# Sheet1.net
KiCad netlist of a schematic drawn in Altium Designer
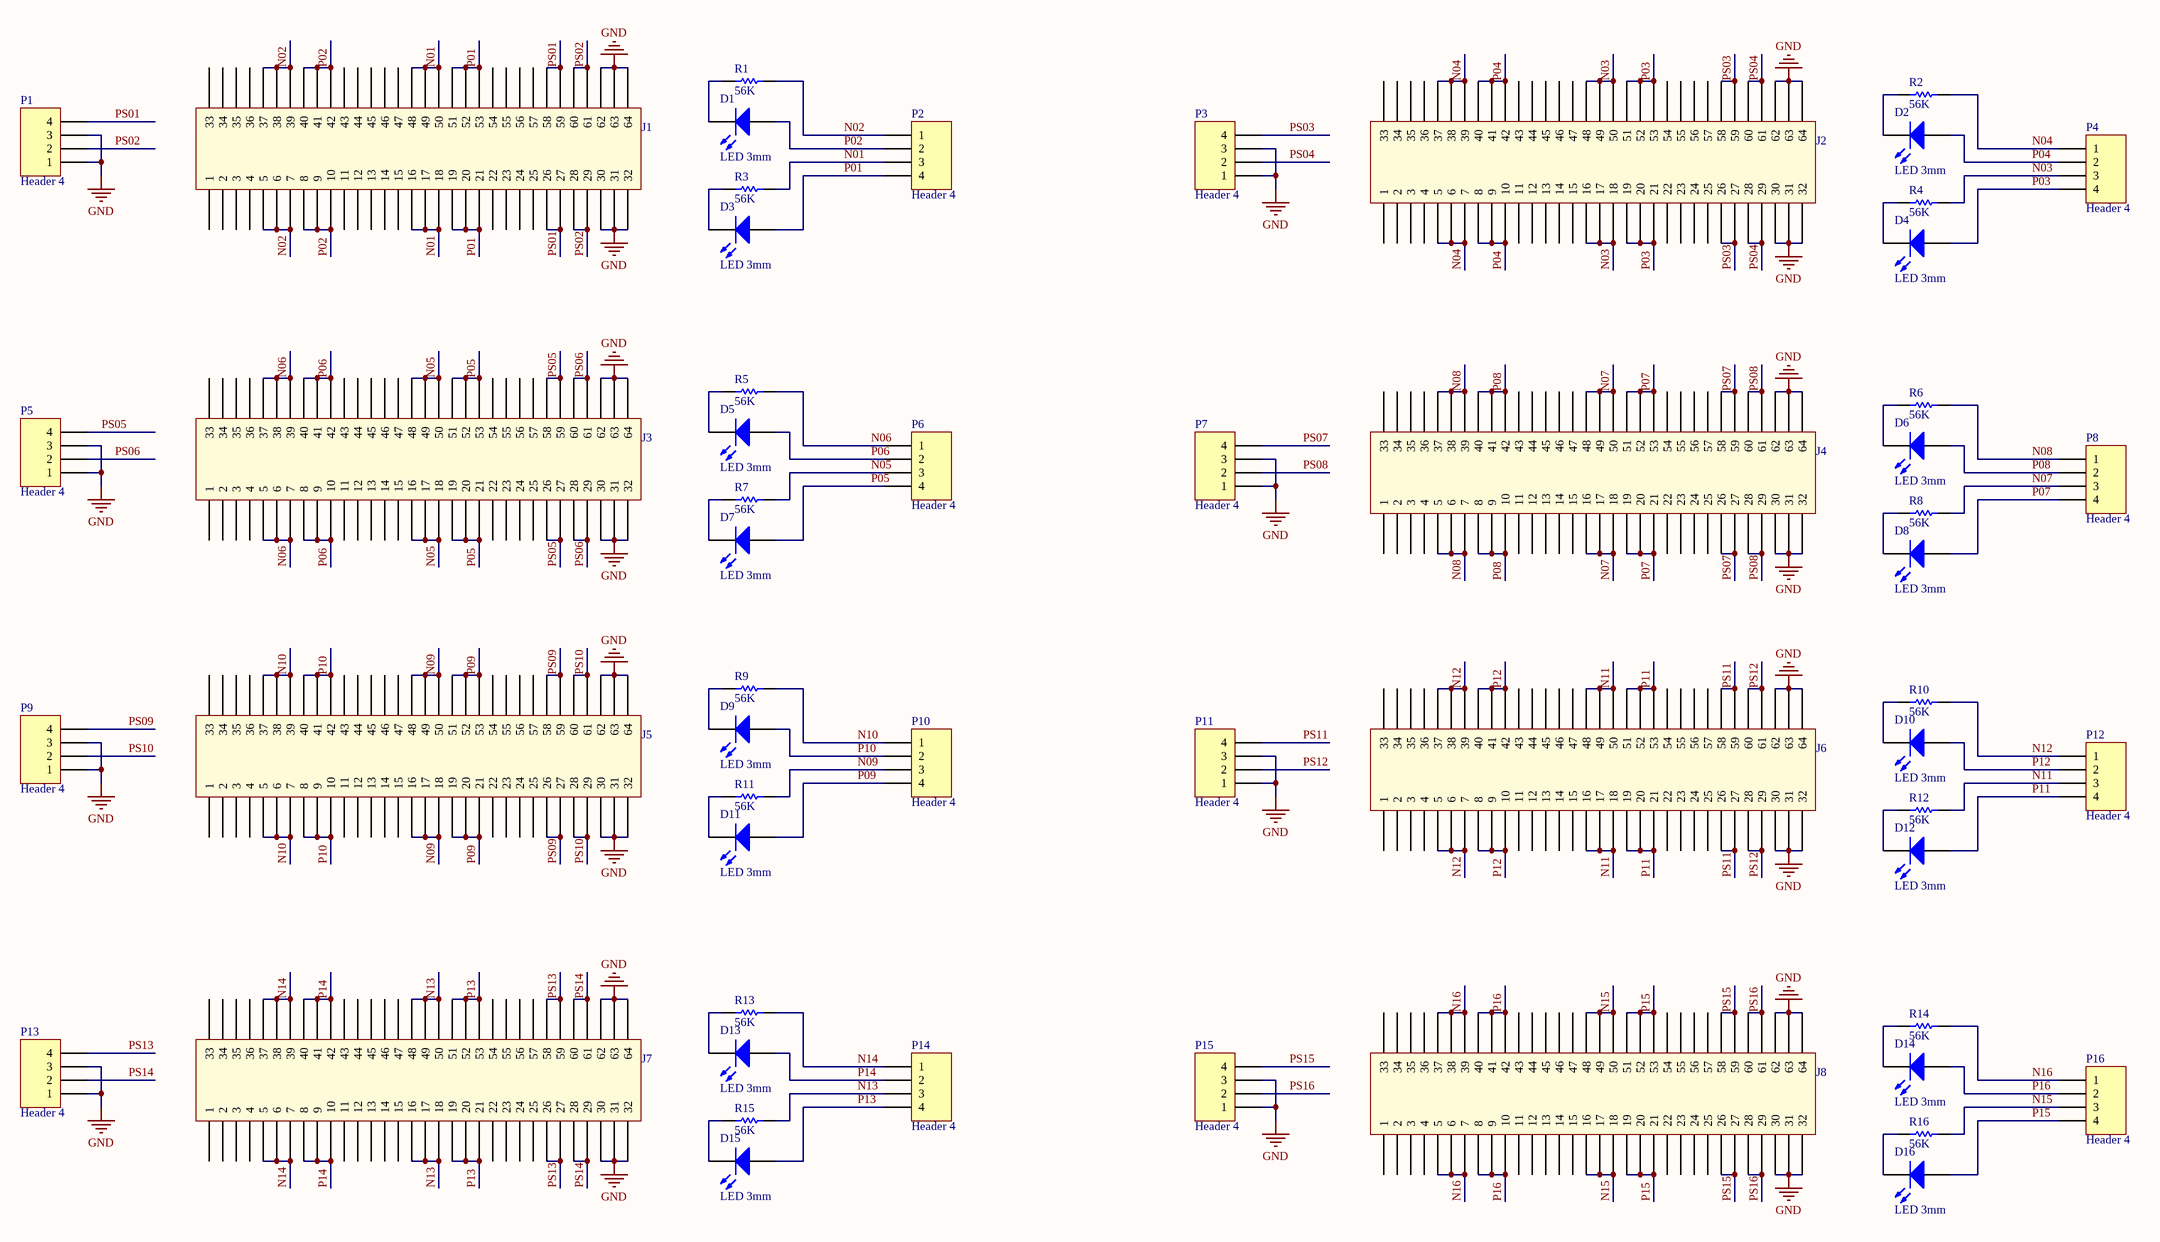
[diagram p0: Sheet1.SchDoc]

(export (version "E")
  (design (tool "Eeschema 10.0.6"))
  (components
    (comp (ref "D1")
      (value "LED 3mm")
      (footprint "Led 3mm")
      (description "Typical INFRARED GaAs LED")
      (fields (field (name "PUBLISHER") "Altium Limited"))
      (libsource (lib "Miscellaneous Devices") (part "LED0"))
    )
    (comp (ref "D2")
      (value "LED 3mm")
      (footprint "Led 3mm")
      (description "Typical INFRARED GaAs LED")
      (fields (field (name "PUBLISHER") "Altium Limited"))
      (libsource (lib "Miscellaneous Devices") (part "LED0"))
    )
    (comp (ref "D3")
      (value "LED 3mm")
      (footprint "Led 3mm")
      (description "Typical INFRARED GaAs LED")
      (fields (field (name "PUBLISHER") "Altium Limited"))
      (libsource (lib "Miscellaneous Devices") (part "LED0"))
    )
    (comp (ref "D4")
      (value "LED 3mm")
      (footprint "Led 3mm")
      (description "Typical INFRARED GaAs LED")
      (fields (field (name "PUBLISHER") "Altium Limited"))
      (libsource (lib "Miscellaneous Devices") (part "LED0"))
    )
    (comp (ref "D5")
      (value "LED 3mm")
      (footprint "Led 3mm")
      (description "Typical INFRARED GaAs LED")
      (fields (field (name "PUBLISHER") "Altium Limited"))
      (libsource (lib "Miscellaneous Devices") (part "LED0"))
    )
    (comp (ref "D6")
      (value "LED 3mm")
      (footprint "Led 3mm")
      (description "Typical INFRARED GaAs LED")
      (fields (field (name "PUBLISHER") "Altium Limited"))
      (libsource (lib "Miscellaneous Devices") (part "LED0"))
    )
    (comp (ref "D7")
      (value "LED 3mm")
      (footprint "Led 3mm")
      (description "Typical INFRARED GaAs LED")
      (fields (field (name "PUBLISHER") "Altium Limited"))
      (libsource (lib "Miscellaneous Devices") (part "LED0"))
    )
    (comp (ref "D8")
      (value "LED 3mm")
      (footprint "Led 3mm")
      (description "Typical INFRARED GaAs LED")
      (fields (field (name "PUBLISHER") "Altium Limited"))
      (libsource (lib "Miscellaneous Devices") (part "LED0"))
    )
    (comp (ref "D9")
      (value "LED 3mm")
      (footprint "Led 3mm")
      (description "Typical INFRARED GaAs LED")
      (fields (field (name "PUBLISHER") "Altium Limited"))
      (libsource (lib "Miscellaneous Devices") (part "LED0"))
    )
    (comp (ref "D10")
      (value "LED 3mm")
      (footprint "Led 3mm")
      (description "Typical INFRARED GaAs LED")
      (fields (field (name "PUBLISHER") "Altium Limited"))
      (libsource (lib "Miscellaneous Devices") (part "LED0"))
    )
    (comp (ref "D11")
      (value "LED 3mm")
      (footprint "Led 3mm")
      (description "Typical INFRARED GaAs LED")
      (fields (field (name "PUBLISHER") "Altium Limited"))
      (libsource (lib "Miscellaneous Devices") (part "LED0"))
    )
    (comp (ref "D12")
      (value "LED 3mm")
      (footprint "Led 3mm")
      (description "Typical INFRARED GaAs LED")
      (fields (field (name "PUBLISHER") "Altium Limited"))
      (libsource (lib "Miscellaneous Devices") (part "LED0"))
    )
    (comp (ref "D13")
      (value "LED 3mm")
      (footprint "Led 3mm")
      (description "Typical INFRARED GaAs LED")
      (fields (field (name "PUBLISHER") "Altium Limited"))
      (libsource (lib "Miscellaneous Devices") (part "LED0"))
    )
    (comp (ref "D14")
      (value "LED 3mm")
      (footprint "Led 3mm")
      (description "Typical INFRARED GaAs LED")
      (fields (field (name "PUBLISHER") "Altium Limited"))
      (libsource (lib "Miscellaneous Devices") (part "LED0"))
    )
    (comp (ref "D15")
      (value "LED 3mm")
      (footprint "Led 3mm")
      (description "Typical INFRARED GaAs LED")
      (fields (field (name "PUBLISHER") "Altium Limited"))
      (libsource (lib "Miscellaneous Devices") (part "LED0"))
    )
    (comp (ref "D16")
      (value "LED 3mm")
      (footprint "Led 3mm")
      (description "Typical INFRARED GaAs LED")
      (fields (field (name "PUBLISHER") "Altium Limited"))
      (libsource (lib "Miscellaneous Devices") (part "LED0"))
    )
    (comp (ref "J1")
      (value "Header 32x2")
      (footprint "Header32x2")
      (libsource (lib "dung_maker_2018") (part "Header 32x2"))
    )
    (comp (ref "J2")
      (value "Header 32x2")
      (footprint "Header32x2")
      (libsource (lib "dung_maker_2018") (part "Header 32x2"))
    )
    (comp (ref "J3")
      (value "Header 32x2")
      (footprint "Header32x2")
      (libsource (lib "dung_maker_2018") (part "Header 32x2"))
    )
    (comp (ref "J4")
      (value "Header 32x2")
      (footprint "Header32x2")
      (libsource (lib "dung_maker_2018") (part "Header 32x2"))
    )
    (comp (ref "J5")
      (value "Header 32x2")
      (footprint "Header32x2")
      (libsource (lib "dung_maker_2018") (part "Header 32x2"))
    )
    (comp (ref "J6")
      (value "Header 32x2")
      (footprint "Header32x2")
      (libsource (lib "dung_maker_2018") (part "Header 32x2"))
    )
    (comp (ref "J7")
      (value "Header 32x2")
      (footprint "Header32x2")
      (libsource (lib "dung_maker_2018") (part "Header 32x2"))
    )
    (comp (ref "J8")
      (value "Header 32x2")
      (footprint "Header32x2")
      (libsource (lib "dung_maker_2018") (part "Header 32x2"))
    )
    (comp (ref "P1")
      (value "Header 4")
      (footprint "CON4")
      (description "Header, 4-Pin")
      (fields (field (name "PUBLISHER") "Altium Limited"))
      (libsource (lib "Miscellaneous Connectors") (part "Header 4"))
    )
    (comp (ref "P2")
      (value "Header 4")
      (footprint "CON4")
      (description "Header, 4-Pin")
      (fields (field (name "PUBLISHER") "Altium Limited"))
      (libsource (lib "") (part "Header 4_1"))
    )
    (comp (ref "P3")
      (value "Header 4")
      (footprint "CON4")
      (description "Header, 4-Pin")
      (fields (field (name "PUBLISHER") "Altium Limited"))
      (libsource (lib "Miscellaneous Connectors") (part "Header 4"))
    )
    (comp (ref "P4")
      (value "Header 4")
      (footprint "CON4")
      (description "Header, 4-Pin")
      (fields (field (name "PUBLISHER") "Altium Limited"))
      (libsource (lib "") (part "Header 4_1"))
    )
    (comp (ref "P5")
      (value "Header 4")
      (footprint "CON4")
      (description "Header, 4-Pin")
      (fields (field (name "PUBLISHER") "Altium Limited"))
      (libsource (lib "Miscellaneous Connectors") (part "Header 4"))
    )
    (comp (ref "P6")
      (value "Header 4")
      (footprint "CON4")
      (description "Header, 4-Pin")
      (fields (field (name "PUBLISHER") "Altium Limited"))
      (libsource (lib "") (part "Header 4_1"))
    )
    (comp (ref "P7")
      (value "Header 4")
      (footprint "CON4")
      (description "Header, 4-Pin")
      (fields (field (name "PUBLISHER") "Altium Limited"))
      (libsource (lib "Miscellaneous Connectors") (part "Header 4"))
    )
    (comp (ref "P8")
      (value "Header 4")
      (footprint "CON4")
      (description "Header, 4-Pin")
      (fields (field (name "PUBLISHER") "Altium Limited"))
      (libsource (lib "") (part "Header 4_1"))
    )
    (comp (ref "P9")
      (value "Header 4")
      (footprint "CON4")
      (description "Header, 4-Pin")
      (fields (field (name "PUBLISHER") "Altium Limited"))
      (libsource (lib "Miscellaneous Connectors") (part "Header 4"))
    )
    (comp (ref "P10")
      (value "Header 4")
      (footprint "CON4")
      (description "Header, 4-Pin")
      (fields (field (name "PUBLISHER") "Altium Limited"))
      (libsource (lib "") (part "Header 4_1"))
    )
    (comp (ref "P11")
      (value "Header 4")
      (footprint "CON4")
      (description "Header, 4-Pin")
      (fields (field (name "PUBLISHER") "Altium Limited"))
      (libsource (lib "Miscellaneous Connectors") (part "Header 4"))
    )
    (comp (ref "P12")
      (value "Header 4")
      (footprint "CON4")
      (description "Header, 4-Pin")
      (fields (field (name "PUBLISHER") "Altium Limited"))
      (libsource (lib "") (part "Header 4_1"))
    )
    (comp (ref "P13")
      (value "Header 4")
      (footprint "CON4")
      (description "Header, 4-Pin")
      (fields (field (name "PUBLISHER") "Altium Limited"))
      (libsource (lib "Miscellaneous Connectors") (part "Header 4"))
    )
    (comp (ref "P14")
      (value "Header 4")
      (footprint "CON4")
      (description "Header, 4-Pin")
      (fields (field (name "PUBLISHER") "Altium Limited"))
      (libsource (lib "") (part "Header 4_1"))
    )
    (comp (ref "P15")
      (value "Header 4")
      (footprint "CON4")
      (description "Header, 4-Pin")
      (fields (field (name "PUBLISHER") "Altium Limited"))
      (libsource (lib "Miscellaneous Connectors") (part "Header 4"))
    )
    (comp (ref "P16")
      (value "Header 4")
      (footprint "CON4")
      (description "Header, 4-Pin")
      (fields (field (name "PUBLISHER") "Altium Limited"))
      (libsource (lib "") (part "Header 4_1"))
    )
    (comp (ref "R1")
      (value "56K")
      (footprint "R1/8W")
      (description "Resistor")
      (fields (field (name "Comment") "Res1") (field (name "PUBLISHER") "Altium Limited"))
      (libsource (lib "Miscellaneous Devices") (part "Res1"))
    )
    (comp (ref "R2")
      (value "56K")
      (footprint "R1/8W")
      (description "Resistor")
      (fields (field (name "Comment") "Res1") (field (name "PUBLISHER") "Altium Limited"))
      (libsource (lib "Miscellaneous Devices") (part "Res1"))
    )
    (comp (ref "R3")
      (value "56K")
      (footprint "R1/8W")
      (description "Resistor")
      (fields (field (name "Comment") "Res1") (field (name "PUBLISHER") "Altium Limited"))
      (libsource (lib "Miscellaneous Devices") (part "Res1"))
    )
    (comp (ref "R4")
      (value "56K")
      (footprint "R1/8W")
      (description "Resistor")
      (fields (field (name "Comment") "Res1") (field (name "PUBLISHER") "Altium Limited"))
      (libsource (lib "Miscellaneous Devices") (part "Res1"))
    )
    (comp (ref "R5")
      (value "56K")
      (footprint "R1/8W")
      (description "Resistor")
      (fields (field (name "Comment") "Res1") (field (name "PUBLISHER") "Altium Limited"))
      (libsource (lib "Miscellaneous Devices") (part "Res1"))
    )
    (comp (ref "R6")
      (value "56K")
      (footprint "R1/8W")
      (description "Resistor")
      (fields (field (name "Comment") "Res1") (field (name "PUBLISHER") "Altium Limited"))
      (libsource (lib "Miscellaneous Devices") (part "Res1"))
    )
    (comp (ref "R7")
      (value "56K")
      (footprint "R1/8W")
      (description "Resistor")
      (fields (field (name "Comment") "Res1") (field (name "PUBLISHER") "Altium Limited"))
      (libsource (lib "Miscellaneous Devices") (part "Res1"))
    )
    (comp (ref "R8")
      (value "56K")
      (footprint "R1/8W")
      (description "Resistor")
      (fields (field (name "Comment") "Res1") (field (name "PUBLISHER") "Altium Limited"))
      (libsource (lib "Miscellaneous Devices") (part "Res1"))
    )
    (comp (ref "R9")
      (value "56K")
      (footprint "R1/8W")
      (description "Resistor")
      (fields (field (name "Comment") "Res1") (field (name "PUBLISHER") "Altium Limited"))
      (libsource (lib "Miscellaneous Devices") (part "Res1"))
    )
    (comp (ref "R10")
      (value "56K")
      (footprint "R1/8W")
      (description "Resistor")
      (fields (field (name "Comment") "Res1") (field (name "PUBLISHER") "Altium Limited"))
      (libsource (lib "Miscellaneous Devices") (part "Res1"))
    )
    (comp (ref "R11")
      (value "56K")
      (footprint "R1/8W")
      (description "Resistor")
      (fields (field (name "Comment") "Res1") (field (name "PUBLISHER") "Altium Limited"))
      (libsource (lib "Miscellaneous Devices") (part "Res1"))
    )
    (comp (ref "R12")
      (value "56K")
      (footprint "R1/8W")
      (description "Resistor")
      (fields (field (name "Comment") "Res1") (field (name "PUBLISHER") "Altium Limited"))
      (libsource (lib "Miscellaneous Devices") (part "Res1"))
    )
    (comp (ref "R13")
      (value "56K")
      (footprint "R1/8W")
      (description "Resistor")
      (fields (field (name "Comment") "Res1") (field (name "PUBLISHER") "Altium Limited"))
      (libsource (lib "Miscellaneous Devices") (part "Res1"))
    )
    (comp (ref "R14")
      (value "56K")
      (footprint "R1/8W")
      (description "Resistor")
      (fields (field (name "Comment") "Res1") (field (name "PUBLISHER") "Altium Limited"))
      (libsource (lib "Miscellaneous Devices") (part "Res1"))
    )
    (comp (ref "R15")
      (value "56K")
      (footprint "R1/8W")
      (description "Resistor")
      (fields (field (name "Comment") "Res1") (field (name "PUBLISHER") "Altium Limited"))
      (libsource (lib "Miscellaneous Devices") (part "Res1"))
    )
    (comp (ref "R16")
      (value "56K")
      (footprint "R1/8W")
      (description "Resistor")
      (fields (field (name "Comment") "Res1") (field (name "PUBLISHER") "Altium Limited"))
      (libsource (lib "Miscellaneous Devices") (part "Res1"))
    )
  )
  (nets
    (net (code "1") (name "/N01") (class "Default")
      (node (ref "J1") (pin "16") (pinfunction "16_16") (pintype "passive"))
      (node (ref "J1") (pin "17") (pinfunction "17_17") (pintype "passive"))
      (node (ref "J1") (pin "18") (pinfunction "18_18") (pintype "passive"))
      (node (ref "J1") (pin "48") (pinfunction "48_48") (pintype "passive"))
      (node (ref "J1") (pin "49") (pinfunction "49_49") (pintype "passive"))
      (node (ref "J1") (pin "50") (pinfunction "50_50") (pintype "passive"))
      (node (ref "P2") (pin "3") (pinfunction "3_3") (pintype "passive"))
      (node (ref "R3") (pin "1") (pinfunction "1_1") (pintype "passive"))
    )
    (net (code "2") (name "/N02") (class "Default")
      (node (ref "J1") (pin "37") (pinfunction "37_37") (pintype "passive"))
      (node (ref "J1") (pin "38") (pinfunction "38_38") (pintype "passive"))
      (node (ref "J1") (pin "39") (pinfunction "39_39") (pintype "passive"))
      (node (ref "J1") (pin "5") (pinfunction "5_5") (pintype "passive"))
      (node (ref "J1") (pin "6") (pinfunction "6_6") (pintype "passive"))
      (node (ref "J1") (pin "7") (pinfunction "7_7") (pintype "passive"))
      (node (ref "P2") (pin "1") (pinfunction "1_1") (pintype "passive"))
      (node (ref "R1") (pin "1") (pinfunction "1_1") (pintype "passive"))
    )
    (net (code "3") (name "/N03") (class "Default")
      (node (ref "J2") (pin "16") (pinfunction "16_16") (pintype "passive"))
      (node (ref "J2") (pin "17") (pinfunction "17_17") (pintype "passive"))
      (node (ref "J2") (pin "18") (pinfunction "18_18") (pintype "passive"))
      (node (ref "J2") (pin "48") (pinfunction "48_48") (pintype "passive"))
      (node (ref "J2") (pin "49") (pinfunction "49_49") (pintype "passive"))
      (node (ref "J2") (pin "50") (pinfunction "50_50") (pintype "passive"))
      (node (ref "P4") (pin "3") (pinfunction "3_3") (pintype "passive"))
      (node (ref "R4") (pin "1") (pinfunction "1_1") (pintype "passive"))
    )
    (net (code "4") (name "/N04") (class "Default")
      (node (ref "J2") (pin "37") (pinfunction "37_37") (pintype "passive"))
      (node (ref "J2") (pin "38") (pinfunction "38_38") (pintype "passive"))
      (node (ref "J2") (pin "39") (pinfunction "39_39") (pintype "passive"))
      (node (ref "J2") (pin "5") (pinfunction "5_5") (pintype "passive"))
      (node (ref "J2") (pin "6") (pinfunction "6_6") (pintype "passive"))
      (node (ref "J2") (pin "7") (pinfunction "7_7") (pintype "passive"))
      (node (ref "P4") (pin "1") (pinfunction "1_1") (pintype "passive"))
      (node (ref "R2") (pin "1") (pinfunction "1_1") (pintype "passive"))
    )
    (net (code "5") (name "/N05") (class "Default")
      (node (ref "J3") (pin "16") (pinfunction "16_16") (pintype "passive"))
      (node (ref "J3") (pin "17") (pinfunction "17_17") (pintype "passive"))
      (node (ref "J3") (pin "18") (pinfunction "18_18") (pintype "passive"))
      (node (ref "J3") (pin "48") (pinfunction "48_48") (pintype "passive"))
      (node (ref "J3") (pin "49") (pinfunction "49_49") (pintype "passive"))
      (node (ref "J3") (pin "50") (pinfunction "50_50") (pintype "passive"))
      (node (ref "P6") (pin "3") (pinfunction "3_3") (pintype "passive"))
      (node (ref "R7") (pin "1") (pinfunction "1_1") (pintype "passive"))
    )
    (net (code "6") (name "/N06") (class "Default")
      (node (ref "J3") (pin "37") (pinfunction "37_37") (pintype "passive"))
      (node (ref "J3") (pin "38") (pinfunction "38_38") (pintype "passive"))
      (node (ref "J3") (pin "39") (pinfunction "39_39") (pintype "passive"))
      (node (ref "J3") (pin "5") (pinfunction "5_5") (pintype "passive"))
      (node (ref "J3") (pin "6") (pinfunction "6_6") (pintype "passive"))
      (node (ref "J3") (pin "7") (pinfunction "7_7") (pintype "passive"))
      (node (ref "P6") (pin "1") (pinfunction "1_1") (pintype "passive"))
      (node (ref "R5") (pin "1") (pinfunction "1_1") (pintype "passive"))
    )
    (net (code "7") (name "/N07") (class "Default")
      (node (ref "J4") (pin "16") (pinfunction "16_16") (pintype "passive"))
      (node (ref "J4") (pin "17") (pinfunction "17_17") (pintype "passive"))
      (node (ref "J4") (pin "18") (pinfunction "18_18") (pintype "passive"))
      (node (ref "J4") (pin "48") (pinfunction "48_48") (pintype "passive"))
      (node (ref "J4") (pin "49") (pinfunction "49_49") (pintype "passive"))
      (node (ref "J4") (pin "50") (pinfunction "50_50") (pintype "passive"))
      (node (ref "P8") (pin "3") (pinfunction "3_3") (pintype "passive"))
      (node (ref "R8") (pin "1") (pinfunction "1_1") (pintype "passive"))
    )
    (net (code "8") (name "/N08") (class "Default")
      (node (ref "J4") (pin "37") (pinfunction "37_37") (pintype "passive"))
      (node (ref "J4") (pin "38") (pinfunction "38_38") (pintype "passive"))
      (node (ref "J4") (pin "39") (pinfunction "39_39") (pintype "passive"))
      (node (ref "J4") (pin "5") (pinfunction "5_5") (pintype "passive"))
      (node (ref "J4") (pin "6") (pinfunction "6_6") (pintype "passive"))
      (node (ref "J4") (pin "7") (pinfunction "7_7") (pintype "passive"))
      (node (ref "P8") (pin "1") (pinfunction "1_1") (pintype "passive"))
      (node (ref "R6") (pin "1") (pinfunction "1_1") (pintype "passive"))
    )
    (net (code "9") (name "/N09") (class "Default")
      (node (ref "J5") (pin "16") (pinfunction "16_16") (pintype "passive"))
      (node (ref "J5") (pin "17") (pinfunction "17_17") (pintype "passive"))
      (node (ref "J5") (pin "18") (pinfunction "18_18") (pintype "passive"))
      (node (ref "J5") (pin "48") (pinfunction "48_48") (pintype "passive"))
      (node (ref "J5") (pin "49") (pinfunction "49_49") (pintype "passive"))
      (node (ref "J5") (pin "50") (pinfunction "50_50") (pintype "passive"))
      (node (ref "P10") (pin "3") (pinfunction "3_3") (pintype "passive"))
      (node (ref "R11") (pin "1") (pinfunction "1_1") (pintype "passive"))
    )
    (net (code "10") (name "/N10") (class "Default")
      (node (ref "J5") (pin "37") (pinfunction "37_37") (pintype "passive"))
      (node (ref "J5") (pin "38") (pinfunction "38_38") (pintype "passive"))
      (node (ref "J5") (pin "39") (pinfunction "39_39") (pintype "passive"))
      (node (ref "J5") (pin "5") (pinfunction "5_5") (pintype "passive"))
      (node (ref "J5") (pin "6") (pinfunction "6_6") (pintype "passive"))
      (node (ref "J5") (pin "7") (pinfunction "7_7") (pintype "passive"))
      (node (ref "P10") (pin "1") (pinfunction "1_1") (pintype "passive"))
      (node (ref "R9") (pin "1") (pinfunction "1_1") (pintype "passive"))
    )
    (net (code "11") (name "/N11") (class "Default")
      (node (ref "J6") (pin "16") (pinfunction "16_16") (pintype "passive"))
      (node (ref "J6") (pin "17") (pinfunction "17_17") (pintype "passive"))
      (node (ref "J6") (pin "18") (pinfunction "18_18") (pintype "passive"))
      (node (ref "J6") (pin "48") (pinfunction "48_48") (pintype "passive"))
      (node (ref "J6") (pin "49") (pinfunction "49_49") (pintype "passive"))
      (node (ref "J6") (pin "50") (pinfunction "50_50") (pintype "passive"))
      (node (ref "P12") (pin "3") (pinfunction "3_3") (pintype "passive"))
      (node (ref "R12") (pin "1") (pinfunction "1_1") (pintype "passive"))
    )
    (net (code "12") (name "/N12") (class "Default")
      (node (ref "J6") (pin "37") (pinfunction "37_37") (pintype "passive"))
      (node (ref "J6") (pin "38") (pinfunction "38_38") (pintype "passive"))
      (node (ref "J6") (pin "39") (pinfunction "39_39") (pintype "passive"))
      (node (ref "J6") (pin "5") (pinfunction "5_5") (pintype "passive"))
      (node (ref "J6") (pin "6") (pinfunction "6_6") (pintype "passive"))
      (node (ref "J6") (pin "7") (pinfunction "7_7") (pintype "passive"))
      (node (ref "P12") (pin "1") (pinfunction "1_1") (pintype "passive"))
      (node (ref "R10") (pin "1") (pinfunction "1_1") (pintype "passive"))
    )
    (net (code "13") (name "/N13") (class "Default")
      (node (ref "J7") (pin "16") (pinfunction "16_16") (pintype "passive"))
      (node (ref "J7") (pin "17") (pinfunction "17_17") (pintype "passive"))
      (node (ref "J7") (pin "18") (pinfunction "18_18") (pintype "passive"))
      (node (ref "J7") (pin "48") (pinfunction "48_48") (pintype "passive"))
      (node (ref "J7") (pin "49") (pinfunction "49_49") (pintype "passive"))
      (node (ref "J7") (pin "50") (pinfunction "50_50") (pintype "passive"))
      (node (ref "P14") (pin "3") (pinfunction "3_3") (pintype "passive"))
      (node (ref "R15") (pin "1") (pinfunction "1_1") (pintype "passive"))
    )
    (net (code "14") (name "/N14") (class "Default")
      (node (ref "J7") (pin "37") (pinfunction "37_37") (pintype "passive"))
      (node (ref "J7") (pin "38") (pinfunction "38_38") (pintype "passive"))
      (node (ref "J7") (pin "39") (pinfunction "39_39") (pintype "passive"))
      (node (ref "J7") (pin "5") (pinfunction "5_5") (pintype "passive"))
      (node (ref "J7") (pin "6") (pinfunction "6_6") (pintype "passive"))
      (node (ref "J7") (pin "7") (pinfunction "7_7") (pintype "passive"))
      (node (ref "P14") (pin "1") (pinfunction "1_1") (pintype "passive"))
      (node (ref "R13") (pin "1") (pinfunction "1_1") (pintype "passive"))
    )
    (net (code "15") (name "/N15") (class "Default")
      (node (ref "J8") (pin "16") (pinfunction "16_16") (pintype "passive"))
      (node (ref "J8") (pin "17") (pinfunction "17_17") (pintype "passive"))
      (node (ref "J8") (pin "18") (pinfunction "18_18") (pintype "passive"))
      (node (ref "J8") (pin "48") (pinfunction "48_48") (pintype "passive"))
      (node (ref "J8") (pin "49") (pinfunction "49_49") (pintype "passive"))
      (node (ref "J8") (pin "50") (pinfunction "50_50") (pintype "passive"))
      (node (ref "P16") (pin "3") (pinfunction "3_3") (pintype "passive"))
      (node (ref "R16") (pin "1") (pinfunction "1_1") (pintype "passive"))
    )
    (net (code "16") (name "/N16") (class "Default")
      (node (ref "J8") (pin "37") (pinfunction "37_37") (pintype "passive"))
      (node (ref "J8") (pin "38") (pinfunction "38_38") (pintype "passive"))
      (node (ref "J8") (pin "39") (pinfunction "39_39") (pintype "passive"))
      (node (ref "J8") (pin "5") (pinfunction "5_5") (pintype "passive"))
      (node (ref "J8") (pin "6") (pinfunction "6_6") (pintype "passive"))
      (node (ref "J8") (pin "7") (pinfunction "7_7") (pintype "passive"))
      (node (ref "P16") (pin "1") (pinfunction "1_1") (pintype "passive"))
      (node (ref "R14") (pin "1") (pinfunction "1_1") (pintype "passive"))
    )
    (net (code "17") (name "/P01") (class "Default")
      (node (ref "D3") (pin "1") (pinfunction "A_1") (pintype "passive"))
      (node (ref "J1") (pin "19") (pinfunction "19_19") (pintype "passive"))
      (node (ref "J1") (pin "20") (pinfunction "20_20") (pintype "passive"))
      (node (ref "J1") (pin "21") (pinfunction "21_21") (pintype "passive"))
      (node (ref "J1") (pin "51") (pinfunction "51_51") (pintype "passive"))
      (node (ref "J1") (pin "52") (pinfunction "52_52") (pintype "passive"))
      (node (ref "J1") (pin "53") (pinfunction "53_53") (pintype "passive"))
      (node (ref "P2") (pin "4") (pinfunction "4_4") (pintype "passive"))
    )
    (net (code "18") (name "/P02") (class "Default")
      (node (ref "D1") (pin "1") (pinfunction "A_1") (pintype "passive"))
      (node (ref "J1") (pin "10") (pinfunction "10_10") (pintype "passive"))
      (node (ref "J1") (pin "40") (pinfunction "40_40") (pintype "passive"))
      (node (ref "J1") (pin "41") (pinfunction "41_41") (pintype "passive"))
      (node (ref "J1") (pin "42") (pinfunction "42_42") (pintype "passive"))
      (node (ref "J1") (pin "8") (pinfunction "8_8") (pintype "passive"))
      (node (ref "J1") (pin "9") (pinfunction "9_9") (pintype "passive"))
      (node (ref "P2") (pin "2") (pinfunction "2_2") (pintype "passive"))
    )
    (net (code "19") (name "/P03") (class "Default")
      (node (ref "D4") (pin "1") (pinfunction "A_1") (pintype "passive"))
      (node (ref "J2") (pin "19") (pinfunction "19_19") (pintype "passive"))
      (node (ref "J2") (pin "20") (pinfunction "20_20") (pintype "passive"))
      (node (ref "J2") (pin "21") (pinfunction "21_21") (pintype "passive"))
      (node (ref "J2") (pin "51") (pinfunction "51_51") (pintype "passive"))
      (node (ref "J2") (pin "52") (pinfunction "52_52") (pintype "passive"))
      (node (ref "J2") (pin "53") (pinfunction "53_53") (pintype "passive"))
      (node (ref "P4") (pin "4") (pinfunction "4_4") (pintype "passive"))
    )
    (net (code "20") (name "/P04") (class "Default")
      (node (ref "D2") (pin "1") (pinfunction "A_1") (pintype "passive"))
      (node (ref "J2") (pin "10") (pinfunction "10_10") (pintype "passive"))
      (node (ref "J2") (pin "40") (pinfunction "40_40") (pintype "passive"))
      (node (ref "J2") (pin "41") (pinfunction "41_41") (pintype "passive"))
      (node (ref "J2") (pin "42") (pinfunction "42_42") (pintype "passive"))
      (node (ref "J2") (pin "8") (pinfunction "8_8") (pintype "passive"))
      (node (ref "J2") (pin "9") (pinfunction "9_9") (pintype "passive"))
      (node (ref "P4") (pin "2") (pinfunction "2_2") (pintype "passive"))
    )
    (net (code "21") (name "/P05") (class "Default")
      (node (ref "D7") (pin "1") (pinfunction "A_1") (pintype "passive"))
      (node (ref "J3") (pin "19") (pinfunction "19_19") (pintype "passive"))
      (node (ref "J3") (pin "20") (pinfunction "20_20") (pintype "passive"))
      (node (ref "J3") (pin "21") (pinfunction "21_21") (pintype "passive"))
      (node (ref "J3") (pin "51") (pinfunction "51_51") (pintype "passive"))
      (node (ref "J3") (pin "52") (pinfunction "52_52") (pintype "passive"))
      (node (ref "J3") (pin "53") (pinfunction "53_53") (pintype "passive"))
      (node (ref "P6") (pin "4") (pinfunction "4_4") (pintype "passive"))
    )
    (net (code "22") (name "/P06") (class "Default")
      (node (ref "D5") (pin "1") (pinfunction "A_1") (pintype "passive"))
      (node (ref "J3") (pin "10") (pinfunction "10_10") (pintype "passive"))
      (node (ref "J3") (pin "40") (pinfunction "40_40") (pintype "passive"))
      (node (ref "J3") (pin "41") (pinfunction "41_41") (pintype "passive"))
      (node (ref "J3") (pin "42") (pinfunction "42_42") (pintype "passive"))
      (node (ref "J3") (pin "8") (pinfunction "8_8") (pintype "passive"))
      (node (ref "J3") (pin "9") (pinfunction "9_9") (pintype "passive"))
      (node (ref "P6") (pin "2") (pinfunction "2_2") (pintype "passive"))
    )
    (net (code "23") (name "/P07") (class "Default")
      (node (ref "D8") (pin "1") (pinfunction "A_1") (pintype "passive"))
      (node (ref "J4") (pin "19") (pinfunction "19_19") (pintype "passive"))
      (node (ref "J4") (pin "20") (pinfunction "20_20") (pintype "passive"))
      (node (ref "J4") (pin "21") (pinfunction "21_21") (pintype "passive"))
      (node (ref "J4") (pin "51") (pinfunction "51_51") (pintype "passive"))
      (node (ref "J4") (pin "52") (pinfunction "52_52") (pintype "passive"))
      (node (ref "J4") (pin "53") (pinfunction "53_53") (pintype "passive"))
      (node (ref "P8") (pin "4") (pinfunction "4_4") (pintype "passive"))
    )
    (net (code "24") (name "/P08") (class "Default")
      (node (ref "D6") (pin "1") (pinfunction "A_1") (pintype "passive"))
      (node (ref "J4") (pin "10") (pinfunction "10_10") (pintype "passive"))
      (node (ref "J4") (pin "40") (pinfunction "40_40") (pintype "passive"))
      (node (ref "J4") (pin "41") (pinfunction "41_41") (pintype "passive"))
      (node (ref "J4") (pin "42") (pinfunction "42_42") (pintype "passive"))
      (node (ref "J4") (pin "8") (pinfunction "8_8") (pintype "passive"))
      (node (ref "J4") (pin "9") (pinfunction "9_9") (pintype "passive"))
      (node (ref "P8") (pin "2") (pinfunction "2_2") (pintype "passive"))
    )
    (net (code "25") (name "/P09") (class "Default")
      (node (ref "D11") (pin "1") (pinfunction "A_1") (pintype "passive"))
      (node (ref "J5") (pin "19") (pinfunction "19_19") (pintype "passive"))
      (node (ref "J5") (pin "20") (pinfunction "20_20") (pintype "passive"))
      (node (ref "J5") (pin "21") (pinfunction "21_21") (pintype "passive"))
      (node (ref "J5") (pin "51") (pinfunction "51_51") (pintype "passive"))
      (node (ref "J5") (pin "52") (pinfunction "52_52") (pintype "passive"))
      (node (ref "J5") (pin "53") (pinfunction "53_53") (pintype "passive"))
      (node (ref "P10") (pin "4") (pinfunction "4_4") (pintype "passive"))
    )
    (net (code "26") (name "/P10") (class "Default")
      (node (ref "D9") (pin "1") (pinfunction "A_1") (pintype "passive"))
      (node (ref "J5") (pin "10") (pinfunction "10_10") (pintype "passive"))
      (node (ref "J5") (pin "40") (pinfunction "40_40") (pintype "passive"))
      (node (ref "J5") (pin "41") (pinfunction "41_41") (pintype "passive"))
      (node (ref "J5") (pin "42") (pinfunction "42_42") (pintype "passive"))
      (node (ref "J5") (pin "8") (pinfunction "8_8") (pintype "passive"))
      (node (ref "J5") (pin "9") (pinfunction "9_9") (pintype "passive"))
      (node (ref "P10") (pin "2") (pinfunction "2_2") (pintype "passive"))
    )
    (net (code "27") (name "/P11") (class "Default")
      (node (ref "D12") (pin "1") (pinfunction "A_1") (pintype "passive"))
      (node (ref "J6") (pin "19") (pinfunction "19_19") (pintype "passive"))
      (node (ref "J6") (pin "20") (pinfunction "20_20") (pintype "passive"))
      (node (ref "J6") (pin "21") (pinfunction "21_21") (pintype "passive"))
      (node (ref "J6") (pin "51") (pinfunction "51_51") (pintype "passive"))
      (node (ref "J6") (pin "52") (pinfunction "52_52") (pintype "passive"))
      (node (ref "J6") (pin "53") (pinfunction "53_53") (pintype "passive"))
      (node (ref "P12") (pin "4") (pinfunction "4_4") (pintype "passive"))
    )
    (net (code "28") (name "/P12") (class "Default")
      (node (ref "D10") (pin "1") (pinfunction "A_1") (pintype "passive"))
      (node (ref "J6") (pin "10") (pinfunction "10_10") (pintype "passive"))
      (node (ref "J6") (pin "40") (pinfunction "40_40") (pintype "passive"))
      (node (ref "J6") (pin "41") (pinfunction "41_41") (pintype "passive"))
      (node (ref "J6") (pin "42") (pinfunction "42_42") (pintype "passive"))
      (node (ref "J6") (pin "8") (pinfunction "8_8") (pintype "passive"))
      (node (ref "J6") (pin "9") (pinfunction "9_9") (pintype "passive"))
      (node (ref "P12") (pin "2") (pinfunction "2_2") (pintype "passive"))
    )
    (net (code "29") (name "/P13") (class "Default")
      (node (ref "D15") (pin "1") (pinfunction "A_1") (pintype "passive"))
      (node (ref "J7") (pin "19") (pinfunction "19_19") (pintype "passive"))
      (node (ref "J7") (pin "20") (pinfunction "20_20") (pintype "passive"))
      (node (ref "J7") (pin "21") (pinfunction "21_21") (pintype "passive"))
      (node (ref "J7") (pin "51") (pinfunction "51_51") (pintype "passive"))
      (node (ref "J7") (pin "52") (pinfunction "52_52") (pintype "passive"))
      (node (ref "J7") (pin "53") (pinfunction "53_53") (pintype "passive"))
      (node (ref "P14") (pin "4") (pinfunction "4_4") (pintype "passive"))
    )
    (net (code "30") (name "/P14") (class "Default")
      (node (ref "D13") (pin "1") (pinfunction "A_1") (pintype "passive"))
      (node (ref "J7") (pin "10") (pinfunction "10_10") (pintype "passive"))
      (node (ref "J7") (pin "40") (pinfunction "40_40") (pintype "passive"))
      (node (ref "J7") (pin "41") (pinfunction "41_41") (pintype "passive"))
      (node (ref "J7") (pin "42") (pinfunction "42_42") (pintype "passive"))
      (node (ref "J7") (pin "8") (pinfunction "8_8") (pintype "passive"))
      (node (ref "J7") (pin "9") (pinfunction "9_9") (pintype "passive"))
      (node (ref "P14") (pin "2") (pinfunction "2_2") (pintype "passive"))
    )
    (net (code "31") (name "/P15") (class "Default")
      (node (ref "D16") (pin "1") (pinfunction "A_1") (pintype "passive"))
      (node (ref "J8") (pin "19") (pinfunction "19_19") (pintype "passive"))
      (node (ref "J8") (pin "20") (pinfunction "20_20") (pintype "passive"))
      (node (ref "J8") (pin "21") (pinfunction "21_21") (pintype "passive"))
      (node (ref "J8") (pin "51") (pinfunction "51_51") (pintype "passive"))
      (node (ref "J8") (pin "52") (pinfunction "52_52") (pintype "passive"))
      (node (ref "J8") (pin "53") (pinfunction "53_53") (pintype "passive"))
      (node (ref "P16") (pin "4") (pinfunction "4_4") (pintype "passive"))
    )
    (net (code "32") (name "/P16") (class "Default")
      (node (ref "D14") (pin "1") (pinfunction "A_1") (pintype "passive"))
      (node (ref "J8") (pin "10") (pinfunction "10_10") (pintype "passive"))
      (node (ref "J8") (pin "40") (pinfunction "40_40") (pintype "passive"))
      (node (ref "J8") (pin "41") (pinfunction "41_41") (pintype "passive"))
      (node (ref "J8") (pin "42") (pinfunction "42_42") (pintype "passive"))
      (node (ref "J8") (pin "8") (pinfunction "8_8") (pintype "passive"))
      (node (ref "J8") (pin "9") (pinfunction "9_9") (pintype "passive"))
      (node (ref "P16") (pin "2") (pinfunction "2_2") (pintype "passive"))
    )
    (net (code "33") (name "/PS01") (class "Default")
      (node (ref "J1") (pin "26") (pinfunction "26_26") (pintype "passive"))
      (node (ref "J1") (pin "27") (pinfunction "27_27") (pintype "passive"))
      (node (ref "J1") (pin "58") (pinfunction "58_58") (pintype "passive"))
      (node (ref "J1") (pin "59") (pinfunction "59_59") (pintype "passive"))
      (node (ref "P1") (pin "4") (pinfunction "4_4") (pintype "passive"))
    )
    (net (code "34") (name "/PS02") (class "Default")
      (node (ref "J1") (pin "28") (pinfunction "28_28") (pintype "passive"))
      (node (ref "J1") (pin "29") (pinfunction "29_29") (pintype "passive"))
      (node (ref "J1") (pin "60") (pinfunction "60_60") (pintype "passive"))
      (node (ref "J1") (pin "61") (pinfunction "61_61") (pintype "passive"))
      (node (ref "P1") (pin "2") (pinfunction "2_2") (pintype "passive"))
    )
    (net (code "35") (name "/PS03") (class "Default")
      (node (ref "J2") (pin "26") (pinfunction "26_26") (pintype "passive"))
      (node (ref "J2") (pin "27") (pinfunction "27_27") (pintype "passive"))
      (node (ref "J2") (pin "58") (pinfunction "58_58") (pintype "passive"))
      (node (ref "J2") (pin "59") (pinfunction "59_59") (pintype "passive"))
      (node (ref "P3") (pin "4") (pinfunction "4_4") (pintype "passive"))
    )
    (net (code "36") (name "/PS04") (class "Default")
      (node (ref "J2") (pin "28") (pinfunction "28_28") (pintype "passive"))
      (node (ref "J2") (pin "29") (pinfunction "29_29") (pintype "passive"))
      (node (ref "J2") (pin "60") (pinfunction "60_60") (pintype "passive"))
      (node (ref "J2") (pin "61") (pinfunction "61_61") (pintype "passive"))
      (node (ref "P3") (pin "2") (pinfunction "2_2") (pintype "passive"))
    )
    (net (code "37") (name "/PS05") (class "Default")
      (node (ref "J3") (pin "26") (pinfunction "26_26") (pintype "passive"))
      (node (ref "J3") (pin "27") (pinfunction "27_27") (pintype "passive"))
      (node (ref "J3") (pin "58") (pinfunction "58_58") (pintype "passive"))
      (node (ref "J3") (pin "59") (pinfunction "59_59") (pintype "passive"))
      (node (ref "P5") (pin "4") (pinfunction "4_4") (pintype "passive"))
    )
    (net (code "38") (name "/PS06") (class "Default")
      (node (ref "J3") (pin "28") (pinfunction "28_28") (pintype "passive"))
      (node (ref "J3") (pin "29") (pinfunction "29_29") (pintype "passive"))
      (node (ref "J3") (pin "60") (pinfunction "60_60") (pintype "passive"))
      (node (ref "J3") (pin "61") (pinfunction "61_61") (pintype "passive"))
      (node (ref "P5") (pin "2") (pinfunction "2_2") (pintype "passive"))
    )
    (net (code "39") (name "/PS07") (class "Default")
      (node (ref "J4") (pin "26") (pinfunction "26_26") (pintype "passive"))
      (node (ref "J4") (pin "27") (pinfunction "27_27") (pintype "passive"))
      (node (ref "J4") (pin "58") (pinfunction "58_58") (pintype "passive"))
      (node (ref "J4") (pin "59") (pinfunction "59_59") (pintype "passive"))
      (node (ref "P7") (pin "4") (pinfunction "4_4") (pintype "passive"))
    )
    (net (code "40") (name "/PS08") (class "Default")
      (node (ref "J4") (pin "28") (pinfunction "28_28") (pintype "passive"))
      (node (ref "J4") (pin "29") (pinfunction "29_29") (pintype "passive"))
      (node (ref "J4") (pin "60") (pinfunction "60_60") (pintype "passive"))
      (node (ref "J4") (pin "61") (pinfunction "61_61") (pintype "passive"))
      (node (ref "P7") (pin "2") (pinfunction "2_2") (pintype "passive"))
    )
    (net (code "41") (name "/PS09") (class "Default")
      (node (ref "J5") (pin "26") (pinfunction "26_26") (pintype "passive"))
      (node (ref "J5") (pin "27") (pinfunction "27_27") (pintype "passive"))
      (node (ref "J5") (pin "58") (pinfunction "58_58") (pintype "passive"))
      (node (ref "J5") (pin "59") (pinfunction "59_59") (pintype "passive"))
      (node (ref "P9") (pin "4") (pinfunction "4_4") (pintype "passive"))
    )
    (net (code "42") (name "/PS10") (class "Default")
      (node (ref "J5") (pin "28") (pinfunction "28_28") (pintype "passive"))
      (node (ref "J5") (pin "29") (pinfunction "29_29") (pintype "passive"))
      (node (ref "J5") (pin "60") (pinfunction "60_60") (pintype "passive"))
      (node (ref "J5") (pin "61") (pinfunction "61_61") (pintype "passive"))
      (node (ref "P9") (pin "2") (pinfunction "2_2") (pintype "passive"))
    )
    (net (code "43") (name "/PS11") (class "Default")
      (node (ref "J6") (pin "26") (pinfunction "26_26") (pintype "passive"))
      (node (ref "J6") (pin "27") (pinfunction "27_27") (pintype "passive"))
      (node (ref "J6") (pin "58") (pinfunction "58_58") (pintype "passive"))
      (node (ref "J6") (pin "59") (pinfunction "59_59") (pintype "passive"))
      (node (ref "P11") (pin "4") (pinfunction "4_4") (pintype "passive"))
    )
    (net (code "44") (name "/PS12") (class "Default")
      (node (ref "J6") (pin "28") (pinfunction "28_28") (pintype "passive"))
      (node (ref "J6") (pin "29") (pinfunction "29_29") (pintype "passive"))
      (node (ref "J6") (pin "60") (pinfunction "60_60") (pintype "passive"))
      (node (ref "J6") (pin "61") (pinfunction "61_61") (pintype "passive"))
      (node (ref "P11") (pin "2") (pinfunction "2_2") (pintype "passive"))
    )
    (net (code "45") (name "/PS13") (class "Default")
      (node (ref "J7") (pin "26") (pinfunction "26_26") (pintype "passive"))
      (node (ref "J7") (pin "27") (pinfunction "27_27") (pintype "passive"))
      (node (ref "J7") (pin "58") (pinfunction "58_58") (pintype "passive"))
      (node (ref "J7") (pin "59") (pinfunction "59_59") (pintype "passive"))
      (node (ref "P13") (pin "4") (pinfunction "4_4") (pintype "passive"))
    )
    (net (code "46") (name "/PS14") (class "Default")
      (node (ref "J7") (pin "28") (pinfunction "28_28") (pintype "passive"))
      (node (ref "J7") (pin "29") (pinfunction "29_29") (pintype "passive"))
      (node (ref "J7") (pin "60") (pinfunction "60_60") (pintype "passive"))
      (node (ref "J7") (pin "61") (pinfunction "61_61") (pintype "passive"))
      (node (ref "P13") (pin "2") (pinfunction "2_2") (pintype "passive"))
    )
    (net (code "47") (name "/PS15") (class "Default")
      (node (ref "J8") (pin "26") (pinfunction "26_26") (pintype "passive"))
      (node (ref "J8") (pin "27") (pinfunction "27_27") (pintype "passive"))
      (node (ref "J8") (pin "58") (pinfunction "58_58") (pintype "passive"))
      (node (ref "J8") (pin "59") (pinfunction "59_59") (pintype "passive"))
      (node (ref "P15") (pin "4") (pinfunction "4_4") (pintype "passive"))
    )
    (net (code "48") (name "/PS16") (class "Default")
      (node (ref "J8") (pin "28") (pinfunction "28_28") (pintype "passive"))
      (node (ref "J8") (pin "29") (pinfunction "29_29") (pintype "passive"))
      (node (ref "J8") (pin "60") (pinfunction "60_60") (pintype "passive"))
      (node (ref "J8") (pin "61") (pinfunction "61_61") (pintype "passive"))
      (node (ref "P15") (pin "2") (pinfunction "2_2") (pintype "passive"))
    )
    (net (code "49") (name "GND") (class "Default")
      (node (ref "J1") (pin "30") (pinfunction "30_30") (pintype "passive"))
      (node (ref "J1") (pin "31") (pinfunction "31_31") (pintype "passive"))
      (node (ref "J1") (pin "32") (pinfunction "32_32") (pintype "passive"))
      (node (ref "J1") (pin "62") (pinfunction "62_62") (pintype "passive"))
      (node (ref "J1") (pin "63") (pinfunction "63_63") (pintype "passive"))
      (node (ref "J1") (pin "64") (pinfunction "64_64") (pintype "passive"))
      (node (ref "J2") (pin "30") (pinfunction "30_30") (pintype "passive"))
      (node (ref "J2") (pin "31") (pinfunction "31_31") (pintype "passive"))
      (node (ref "J2") (pin "32") (pinfunction "32_32") (pintype "passive"))
      (node (ref "J2") (pin "62") (pinfunction "62_62") (pintype "passive"))
      (node (ref "J2") (pin "63") (pinfunction "63_63") (pintype "passive"))
      (node (ref "J2") (pin "64") (pinfunction "64_64") (pintype "passive"))
      (node (ref "J3") (pin "30") (pinfunction "30_30") (pintype "passive"))
      (node (ref "J3") (pin "31") (pinfunction "31_31") (pintype "passive"))
      (node (ref "J3") (pin "32") (pinfunction "32_32") (pintype "passive"))
      (node (ref "J3") (pin "62") (pinfunction "62_62") (pintype "passive"))
      (node (ref "J3") (pin "63") (pinfunction "63_63") (pintype "passive"))
      (node (ref "J3") (pin "64") (pinfunction "64_64") (pintype "passive"))
      (node (ref "J4") (pin "30") (pinfunction "30_30") (pintype "passive"))
      (node (ref "J4") (pin "31") (pinfunction "31_31") (pintype "passive"))
      (node (ref "J4") (pin "32") (pinfunction "32_32") (pintype "passive"))
      (node (ref "J4") (pin "62") (pinfunction "62_62") (pintype "passive"))
      (node (ref "J4") (pin "63") (pinfunction "63_63") (pintype "passive"))
      (node (ref "J4") (pin "64") (pinfunction "64_64") (pintype "passive"))
      (node (ref "J5") (pin "30") (pinfunction "30_30") (pintype "passive"))
      (node (ref "J5") (pin "31") (pinfunction "31_31") (pintype "passive"))
      (node (ref "J5") (pin "32") (pinfunction "32_32") (pintype "passive"))
      (node (ref "J5") (pin "62") (pinfunction "62_62") (pintype "passive"))
      (node (ref "J5") (pin "63") (pinfunction "63_63") (pintype "passive"))
      (node (ref "J5") (pin "64") (pinfunction "64_64") (pintype "passive"))
      (node (ref "J6") (pin "30") (pinfunction "30_30") (pintype "passive"))
      (node (ref "J6") (pin "31") (pinfunction "31_31") (pintype "passive"))
      (node (ref "J6") (pin "32") (pinfunction "32_32") (pintype "passive"))
      (node (ref "J6") (pin "62") (pinfunction "62_62") (pintype "passive"))
      (node (ref "J6") (pin "63") (pinfunction "63_63") (pintype "passive"))
      (node (ref "J6") (pin "64") (pinfunction "64_64") (pintype "passive"))
      (node (ref "J7") (pin "30") (pinfunction "30_30") (pintype "passive"))
      (node (ref "J7") (pin "31") (pinfunction "31_31") (pintype "passive"))
      (node (ref "J7") (pin "32") (pinfunction "32_32") (pintype "passive"))
      (node (ref "J7") (pin "62") (pinfunction "62_62") (pintype "passive"))
      (node (ref "J7") (pin "63") (pinfunction "63_63") (pintype "passive"))
      (node (ref "J7") (pin "64") (pinfunction "64_64") (pintype "passive"))
      (node (ref "J8") (pin "30") (pinfunction "30_30") (pintype "passive"))
      (node (ref "J8") (pin "31") (pinfunction "31_31") (pintype "passive"))
      (node (ref "J8") (pin "32") (pinfunction "32_32") (pintype "passive"))
      (node (ref "J8") (pin "62") (pinfunction "62_62") (pintype "passive"))
      (node (ref "J8") (pin "63") (pinfunction "63_63") (pintype "passive"))
      (node (ref "J8") (pin "64") (pinfunction "64_64") (pintype "passive"))
      (node (ref "P1") (pin "1") (pinfunction "1_1") (pintype "passive"))
      (node (ref "P1") (pin "3") (pinfunction "3_3") (pintype "passive"))
      (node (ref "P11") (pin "1") (pinfunction "1_1") (pintype "passive"))
      (node (ref "P11") (pin "3") (pinfunction "3_3") (pintype "passive"))
      (node (ref "P13") (pin "1") (pinfunction "1_1") (pintype "passive"))
      (node (ref "P13") (pin "3") (pinfunction "3_3") (pintype "passive"))
      (node (ref "P15") (pin "1") (pinfunction "1_1") (pintype "passive"))
      (node (ref "P15") (pin "3") (pinfunction "3_3") (pintype "passive"))
      (node (ref "P3") (pin "1") (pinfunction "1_1") (pintype "passive"))
      (node (ref "P3") (pin "3") (pinfunction "3_3") (pintype "passive"))
      (node (ref "P5") (pin "1") (pinfunction "1_1") (pintype "passive"))
      (node (ref "P5") (pin "3") (pinfunction "3_3") (pintype "passive"))
      (node (ref "P7") (pin "1") (pinfunction "1_1") (pintype "passive"))
      (node (ref "P7") (pin "3") (pinfunction "3_3") (pintype "passive"))
      (node (ref "P9") (pin "1") (pinfunction "1_1") (pintype "passive"))
      (node (ref "P9") (pin "3") (pinfunction "3_3") (pintype "passive"))
    )
    (net (code "50") (name "Net-(D1-K)") (class "Default")
      (node (ref "D1") (pin "2") (pinfunction "K_2") (pintype "passive"))
      (node (ref "R1") (pin "2") (pinfunction "2_2") (pintype "passive"))
    )
    (net (code "51") (name "Net-(D2-K)") (class "Default")
      (node (ref "D2") (pin "2") (pinfunction "K_2") (pintype "passive"))
      (node (ref "R2") (pin "2") (pinfunction "2_2") (pintype "passive"))
    )
    (net (code "52") (name "Net-(D3-K)") (class "Default")
      (node (ref "D3") (pin "2") (pinfunction "K_2") (pintype "passive"))
      (node (ref "R3") (pin "2") (pinfunction "2_2") (pintype "passive"))
    )
    (net (code "53") (name "Net-(D4-K)") (class "Default")
      (node (ref "D4") (pin "2") (pinfunction "K_2") (pintype "passive"))
      (node (ref "R4") (pin "2") (pinfunction "2_2") (pintype "passive"))
    )
    (net (code "54") (name "Net-(D5-K)") (class "Default")
      (node (ref "D5") (pin "2") (pinfunction "K_2") (pintype "passive"))
      (node (ref "R5") (pin "2") (pinfunction "2_2") (pintype "passive"))
    )
    (net (code "55") (name "Net-(D6-K)") (class "Default")
      (node (ref "D6") (pin "2") (pinfunction "K_2") (pintype "passive"))
      (node (ref "R6") (pin "2") (pinfunction "2_2") (pintype "passive"))
    )
    (net (code "56") (name "Net-(D7-K)") (class "Default")
      (node (ref "D7") (pin "2") (pinfunction "K_2") (pintype "passive"))
      (node (ref "R7") (pin "2") (pinfunction "2_2") (pintype "passive"))
    )
    (net (code "57") (name "Net-(D8-K)") (class "Default")
      (node (ref "D8") (pin "2") (pinfunction "K_2") (pintype "passive"))
      (node (ref "R8") (pin "2") (pinfunction "2_2") (pintype "passive"))
    )
    (net (code "58") (name "Net-(D9-K)") (class "Default")
      (node (ref "D9") (pin "2") (pinfunction "K_2") (pintype "passive"))
      (node (ref "R9") (pin "2") (pinfunction "2_2") (pintype "passive"))
    )
    (net (code "59") (name "Net-(D10-K)") (class "Default")
      (node (ref "D10") (pin "2") (pinfunction "K_2") (pintype "passive"))
      (node (ref "R10") (pin "2") (pinfunction "2_2") (pintype "passive"))
    )
    (net (code "60") (name "Net-(D11-K)") (class "Default")
      (node (ref "D11") (pin "2") (pinfunction "K_2") (pintype "passive"))
      (node (ref "R11") (pin "2") (pinfunction "2_2") (pintype "passive"))
    )
    (net (code "61") (name "Net-(D12-K)") (class "Default")
      (node (ref "D12") (pin "2") (pinfunction "K_2") (pintype "passive"))
      (node (ref "R12") (pin "2") (pinfunction "2_2") (pintype "passive"))
    )
    (net (code "62") (name "Net-(D13-K)") (class "Default")
      (node (ref "D13") (pin "2") (pinfunction "K_2") (pintype "passive"))
      (node (ref "R13") (pin "2") (pinfunction "2_2") (pintype "passive"))
    )
    (net (code "63") (name "Net-(D14-K)") (class "Default")
      (node (ref "D14") (pin "2") (pinfunction "K_2") (pintype "passive"))
      (node (ref "R14") (pin "2") (pinfunction "2_2") (pintype "passive"))
    )
    (net (code "64") (name "Net-(D15-K)") (class "Default")
      (node (ref "D15") (pin "2") (pinfunction "K_2") (pintype "passive"))
      (node (ref "R15") (pin "2") (pinfunction "2_2") (pintype "passive"))
    )
    (net (code "65") (name "Net-(D16-K)") (class "Default")
      (node (ref "D16") (pin "2") (pinfunction "K_2") (pintype "passive"))
      (node (ref "R16") (pin "2") (pinfunction "2_2") (pintype "passive"))
    )
    (net (code "66") (name "unconnected-(J1-Pad1)") (class "Default")
      (node (ref "J1") (pin "1") (pinfunction "1_1") (pintype "passive"))
    )
    (net (code "67") (name "unconnected-(J1-Pad2)") (class "Default")
      (node (ref "J1") (pin "2") (pinfunction "2_2") (pintype "passive"))
    )
    (net (code "68") (name "unconnected-(J1-Pad3)") (class "Default")
      (node (ref "J1") (pin "3") (pinfunction "3_3") (pintype "passive"))
    )
    (net (code "69") (name "unconnected-(J1-Pad4)") (class "Default")
      (node (ref "J1") (pin "4") (pinfunction "4_4") (pintype "passive"))
    )
    (net (code "70") (name "unconnected-(J1-Pad11)") (class "Default")
      (node (ref "J1") (pin "11") (pinfunction "11_11") (pintype "passive"))
    )
    (net (code "71") (name "unconnected-(J1-Pad12)") (class "Default")
      (node (ref "J1") (pin "12") (pinfunction "12_12") (pintype "passive"))
    )
    (net (code "72") (name "unconnected-(J1-Pad13)") (class "Default")
      (node (ref "J1") (pin "13") (pinfunction "13_13") (pintype "passive"))
    )
    (net (code "73") (name "unconnected-(J1-Pad14)") (class "Default")
      (node (ref "J1") (pin "14") (pinfunction "14_14") (pintype "passive"))
    )
    (net (code "74") (name "unconnected-(J1-Pad15)") (class "Default")
      (node (ref "J1") (pin "15") (pinfunction "15_15") (pintype "passive"))
    )
    (net (code "75") (name "unconnected-(J1-Pad22)") (class "Default")
      (node (ref "J1") (pin "22") (pinfunction "22_22") (pintype "passive"))
    )
    (net (code "76") (name "unconnected-(J1-Pad23)") (class "Default")
      (node (ref "J1") (pin "23") (pinfunction "23_23") (pintype "passive"))
    )
    (net (code "77") (name "unconnected-(J1-Pad24)") (class "Default")
      (node (ref "J1") (pin "24") (pinfunction "24_24") (pintype "passive"))
    )
    (net (code "78") (name "unconnected-(J1-Pad25)") (class "Default")
      (node (ref "J1") (pin "25") (pinfunction "25_25") (pintype "passive"))
    )
    (net (code "79") (name "unconnected-(J1-Pad33)") (class "Default")
      (node (ref "J1") (pin "33") (pinfunction "33_33") (pintype "passive"))
    )
    (net (code "80") (name "unconnected-(J1-Pad34)") (class "Default")
      (node (ref "J1") (pin "34") (pinfunction "34_34") (pintype "passive"))
    )
    (net (code "81") (name "unconnected-(J1-Pad35)") (class "Default")
      (node (ref "J1") (pin "35") (pinfunction "35_35") (pintype "passive"))
    )
    (net (code "82") (name "unconnected-(J1-Pad36)") (class "Default")
      (node (ref "J1") (pin "36") (pinfunction "36_36") (pintype "passive"))
    )
    (net (code "83") (name "unconnected-(J1-Pad43)") (class "Default")
      (node (ref "J1") (pin "43") (pinfunction "43_43") (pintype "passive"))
    )
    (net (code "84") (name "unconnected-(J1-Pad44)") (class "Default")
      (node (ref "J1") (pin "44") (pinfunction "44_44") (pintype "passive"))
    )
    (net (code "85") (name "unconnected-(J1-Pad45)") (class "Default")
      (node (ref "J1") (pin "45") (pinfunction "45_45") (pintype "passive"))
    )
    (net (code "86") (name "unconnected-(J1-Pad46)") (class "Default")
      (node (ref "J1") (pin "46") (pinfunction "46_46") (pintype "passive"))
    )
    (net (code "87") (name "unconnected-(J1-Pad47)") (class "Default")
      (node (ref "J1") (pin "47") (pinfunction "47_47") (pintype "passive"))
    )
    (net (code "88") (name "unconnected-(J1-Pad54)") (class "Default")
      (node (ref "J1") (pin "54") (pinfunction "54_54") (pintype "passive"))
    )
    (net (code "89") (name "unconnected-(J1-Pad55)") (class "Default")
      (node (ref "J1") (pin "55") (pinfunction "55_55") (pintype "passive"))
    )
    (net (code "90") (name "unconnected-(J1-Pad56)") (class "Default")
      (node (ref "J1") (pin "56") (pinfunction "56_56") (pintype "passive"))
    )
    (net (code "91") (name "unconnected-(J1-Pad57)") (class "Default")
      (node (ref "J1") (pin "57") (pinfunction "57_57") (pintype "passive"))
    )
    (net (code "92") (name "unconnected-(J2-Pad1)") (class "Default")
      (node (ref "J2") (pin "1") (pinfunction "1_1") (pintype "passive"))
    )
    (net (code "93") (name "unconnected-(J2-Pad2)") (class "Default")
      (node (ref "J2") (pin "2") (pinfunction "2_2") (pintype "passive"))
    )
    (net (code "94") (name "unconnected-(J2-Pad3)") (class "Default")
      (node (ref "J2") (pin "3") (pinfunction "3_3") (pintype "passive"))
    )
    (net (code "95") (name "unconnected-(J2-Pad4)") (class "Default")
      (node (ref "J2") (pin "4") (pinfunction "4_4") (pintype "passive"))
    )
    (net (code "96") (name "unconnected-(J2-Pad11)") (class "Default")
      (node (ref "J2") (pin "11") (pinfunction "11_11") (pintype "passive"))
    )
    (net (code "97") (name "unconnected-(J2-Pad12)") (class "Default")
      (node (ref "J2") (pin "12") (pinfunction "12_12") (pintype "passive"))
    )
    (net (code "98") (name "unconnected-(J2-Pad13)") (class "Default")
      (node (ref "J2") (pin "13") (pinfunction "13_13") (pintype "passive"))
    )
    (net (code "99") (name "unconnected-(J2-Pad14)") (class "Default")
      (node (ref "J2") (pin "14") (pinfunction "14_14") (pintype "passive"))
    )
    (net (code "100") (name "unconnected-(J2-Pad15)") (class "Default")
      (node (ref "J2") (pin "15") (pinfunction "15_15") (pintype "passive"))
    )
    (net (code "101") (name "unconnected-(J2-Pad22)") (class "Default")
      (node (ref "J2") (pin "22") (pinfunction "22_22") (pintype "passive"))
    )
    (net (code "102") (name "unconnected-(J2-Pad23)") (class "Default")
      (node (ref "J2") (pin "23") (pinfunction "23_23") (pintype "passive"))
    )
    (net (code "103") (name "unconnected-(J2-Pad24)") (class "Default")
      (node (ref "J2") (pin "24") (pinfunction "24_24") (pintype "passive"))
    )
    (net (code "104") (name "unconnected-(J2-Pad25)") (class "Default")
      (node (ref "J2") (pin "25") (pinfunction "25_25") (pintype "passive"))
    )
    (net (code "105") (name "unconnected-(J2-Pad33)") (class "Default")
      (node (ref "J2") (pin "33") (pinfunction "33_33") (pintype "passive"))
    )
    (net (code "106") (name "unconnected-(J2-Pad34)") (class "Default")
      (node (ref "J2") (pin "34") (pinfunction "34_34") (pintype "passive"))
    )
    (net (code "107") (name "unconnected-(J2-Pad35)") (class "Default")
      (node (ref "J2") (pin "35") (pinfunction "35_35") (pintype "passive"))
    )
    (net (code "108") (name "unconnected-(J2-Pad36)") (class "Default")
      (node (ref "J2") (pin "36") (pinfunction "36_36") (pintype "passive"))
    )
    (net (code "109") (name "unconnected-(J2-Pad43)") (class "Default")
      (node (ref "J2") (pin "43") (pinfunction "43_43") (pintype "passive"))
    )
    (net (code "110") (name "unconnected-(J2-Pad44)") (class "Default")
      (node (ref "J2") (pin "44") (pinfunction "44_44") (pintype "passive"))
    )
    (net (code "111") (name "unconnected-(J2-Pad45)") (class "Default")
      (node (ref "J2") (pin "45") (pinfunction "45_45") (pintype "passive"))
    )
    (net (code "112") (name "unconnected-(J2-Pad46)") (class "Default")
      (node (ref "J2") (pin "46") (pinfunction "46_46") (pintype "passive"))
    )
    (net (code "113") (name "unconnected-(J2-Pad47)") (class "Default")
      (node (ref "J2") (pin "47") (pinfunction "47_47") (pintype "passive"))
    )
    (net (code "114") (name "unconnected-(J2-Pad54)") (class "Default")
      (node (ref "J2") (pin "54") (pinfunction "54_54") (pintype "passive"))
    )
    (net (code "115") (name "unconnected-(J2-Pad55)") (class "Default")
      (node (ref "J2") (pin "55") (pinfunction "55_55") (pintype "passive"))
    )
    (net (code "116") (name "unconnected-(J2-Pad56)") (class "Default")
      (node (ref "J2") (pin "56") (pinfunction "56_56") (pintype "passive"))
    )
    (net (code "117") (name "unconnected-(J2-Pad57)") (class "Default")
      (node (ref "J2") (pin "57") (pinfunction "57_57") (pintype "passive"))
    )
    (net (code "118") (name "unconnected-(J3-Pad1)") (class "Default")
      (node (ref "J3") (pin "1") (pinfunction "1_1") (pintype "passive"))
    )
    (net (code "119") (name "unconnected-(J3-Pad2)") (class "Default")
      (node (ref "J3") (pin "2") (pinfunction "2_2") (pintype "passive"))
    )
    (net (code "120") (name "unconnected-(J3-Pad3)") (class "Default")
      (node (ref "J3") (pin "3") (pinfunction "3_3") (pintype "passive"))
    )
    (net (code "121") (name "unconnected-(J3-Pad4)") (class "Default")
      (node (ref "J3") (pin "4") (pinfunction "4_4") (pintype "passive"))
    )
    (net (code "122") (name "unconnected-(J3-Pad11)") (class "Default")
      (node (ref "J3") (pin "11") (pinfunction "11_11") (pintype "passive"))
    )
    (net (code "123") (name "unconnected-(J3-Pad12)") (class "Default")
      (node (ref "J3") (pin "12") (pinfunction "12_12") (pintype "passive"))
    )
    (net (code "124") (name "unconnected-(J3-Pad13)") (class "Default")
      (node (ref "J3") (pin "13") (pinfunction "13_13") (pintype "passive"))
    )
    (net (code "125") (name "unconnected-(J3-Pad14)") (class "Default")
      (node (ref "J3") (pin "14") (pinfunction "14_14") (pintype "passive"))
    )
    (net (code "126") (name "unconnected-(J3-Pad15)") (class "Default")
      (node (ref "J3") (pin "15") (pinfunction "15_15") (pintype "passive"))
    )
    (net (code "127") (name "unconnected-(J3-Pad22)") (class "Default")
      (node (ref "J3") (pin "22") (pinfunction "22_22") (pintype "passive"))
    )
    (net (code "128") (name "unconnected-(J3-Pad23)") (class "Default")
      (node (ref "J3") (pin "23") (pinfunction "23_23") (pintype "passive"))
    )
    (net (code "129") (name "unconnected-(J3-Pad24)") (class "Default")
      (node (ref "J3") (pin "24") (pinfunction "24_24") (pintype "passive"))
    )
    (net (code "130") (name "unconnected-(J3-Pad25)") (class "Default")
      (node (ref "J3") (pin "25") (pinfunction "25_25") (pintype "passive"))
    )
    (net (code "131") (name "unconnected-(J3-Pad33)") (class "Default")
      (node (ref "J3") (pin "33") (pinfunction "33_33") (pintype "passive"))
    )
    (net (code "132") (name "unconnected-(J3-Pad34)") (class "Default")
      (node (ref "J3") (pin "34") (pinfunction "34_34") (pintype "passive"))
    )
    (net (code "133") (name "unconnected-(J3-Pad35)") (class "Default")
      (node (ref "J3") (pin "35") (pinfunction "35_35") (pintype "passive"))
    )
    (net (code "134") (name "unconnected-(J3-Pad36)") (class "Default")
      (node (ref "J3") (pin "36") (pinfunction "36_36") (pintype "passive"))
    )
    (net (code "135") (name "unconnected-(J3-Pad43)") (class "Default")
      (node (ref "J3") (pin "43") (pinfunction "43_43") (pintype "passive"))
    )
    (net (code "136") (name "unconnected-(J3-Pad44)") (class "Default")
      (node (ref "J3") (pin "44") (pinfunction "44_44") (pintype "passive"))
    )
    (net (code "137") (name "unconnected-(J3-Pad45)") (class "Default")
      (node (ref "J3") (pin "45") (pinfunction "45_45") (pintype "passive"))
    )
    (net (code "138") (name "unconnected-(J3-Pad46)") (class "Default")
      (node (ref "J3") (pin "46") (pinfunction "46_46") (pintype "passive"))
    )
    (net (code "139") (name "unconnected-(J3-Pad47)") (class "Default")
      (node (ref "J3") (pin "47") (pinfunction "47_47") (pintype "passive"))
    )
    (net (code "140") (name "unconnected-(J3-Pad54)") (class "Default")
      (node (ref "J3") (pin "54") (pinfunction "54_54") (pintype "passive"))
    )
    (net (code "141") (name "unconnected-(J3-Pad55)") (class "Default")
      (node (ref "J3") (pin "55") (pinfunction "55_55") (pintype "passive"))
    )
    (net (code "142") (name "unconnected-(J3-Pad56)") (class "Default")
      (node (ref "J3") (pin "56") (pinfunction "56_56") (pintype "passive"))
    )
    (net (code "143") (name "unconnected-(J3-Pad57)") (class "Default")
      (node (ref "J3") (pin "57") (pinfunction "57_57") (pintype "passive"))
    )
    (net (code "144") (name "unconnected-(J4-Pad1)") (class "Default")
      (node (ref "J4") (pin "1") (pinfunction "1_1") (pintype "passive"))
    )
    (net (code "145") (name "unconnected-(J4-Pad2)") (class "Default")
      (node (ref "J4") (pin "2") (pinfunction "2_2") (pintype "passive"))
    )
    (net (code "146") (name "unconnected-(J4-Pad3)") (class "Default")
      (node (ref "J4") (pin "3") (pinfunction "3_3") (pintype "passive"))
    )
    (net (code "147") (name "unconnected-(J4-Pad4)") (class "Default")
      (node (ref "J4") (pin "4") (pinfunction "4_4") (pintype "passive"))
    )
    (net (code "148") (name "unconnected-(J4-Pad11)") (class "Default")
      (node (ref "J4") (pin "11") (pinfunction "11_11") (pintype "passive"))
    )
    (net (code "149") (name "unconnected-(J4-Pad12)") (class "Default")
      (node (ref "J4") (pin "12") (pinfunction "12_12") (pintype "passive"))
    )
    (net (code "150") (name "unconnected-(J4-Pad13)") (class "Default")
      (node (ref "J4") (pin "13") (pinfunction "13_13") (pintype "passive"))
    )
    (net (code "151") (name "unconnected-(J4-Pad14)") (class "Default")
      (node (ref "J4") (pin "14") (pinfunction "14_14") (pintype "passive"))
    )
    (net (code "152") (name "unconnected-(J4-Pad15)") (class "Default")
      (node (ref "J4") (pin "15") (pinfunction "15_15") (pintype "passive"))
    )
    (net (code "153") (name "unconnected-(J4-Pad22)") (class "Default")
      (node (ref "J4") (pin "22") (pinfunction "22_22") (pintype "passive"))
    )
    (net (code "154") (name "unconnected-(J4-Pad23)") (class "Default")
      (node (ref "J4") (pin "23") (pinfunction "23_23") (pintype "passive"))
    )
    (net (code "155") (name "unconnected-(J4-Pad24)") (class "Default")
      (node (ref "J4") (pin "24") (pinfunction "24_24") (pintype "passive"))
    )
    (net (code "156") (name "unconnected-(J4-Pad25)") (class "Default")
      (node (ref "J4") (pin "25") (pinfunction "25_25") (pintype "passive"))
    )
    (net (code "157") (name "unconnected-(J4-Pad33)") (class "Default")
      (node (ref "J4") (pin "33") (pinfunction "33_33") (pintype "passive"))
    )
    (net (code "158") (name "unconnected-(J4-Pad34)") (class "Default")
      (node (ref "J4") (pin "34") (pinfunction "34_34") (pintype "passive"))
    )
    (net (code "159") (name "unconnected-(J4-Pad35)") (class "Default")
      (node (ref "J4") (pin "35") (pinfunction "35_35") (pintype "passive"))
    )
    (net (code "160") (name "unconnected-(J4-Pad36)") (class "Default")
      (node (ref "J4") (pin "36") (pinfunction "36_36") (pintype "passive"))
    )
    (net (code "161") (name "unconnected-(J4-Pad43)") (class "Default")
      (node (ref "J4") (pin "43") (pinfunction "43_43") (pintype "passive"))
    )
    (net (code "162") (name "unconnected-(J4-Pad44)") (class "Default")
      (node (ref "J4") (pin "44") (pinfunction "44_44") (pintype "passive"))
    )
    (net (code "163") (name "unconnected-(J4-Pad45)") (class "Default")
      (node (ref "J4") (pin "45") (pinfunction "45_45") (pintype "passive"))
    )
    (net (code "164") (name "unconnected-(J4-Pad46)") (class "Default")
      (node (ref "J4") (pin "46") (pinfunction "46_46") (pintype "passive"))
    )
    (net (code "165") (name "unconnected-(J4-Pad47)") (class "Default")
      (node (ref "J4") (pin "47") (pinfunction "47_47") (pintype "passive"))
    )
    (net (code "166") (name "unconnected-(J4-Pad54)") (class "Default")
      (node (ref "J4") (pin "54") (pinfunction "54_54") (pintype "passive"))
    )
    (net (code "167") (name "unconnected-(J4-Pad55)") (class "Default")
      (node (ref "J4") (pin "55") (pinfunction "55_55") (pintype "passive"))
    )
    (net (code "168") (name "unconnected-(J4-Pad56)") (class "Default")
      (node (ref "J4") (pin "56") (pinfunction "56_56") (pintype "passive"))
    )
    (net (code "169") (name "unconnected-(J4-Pad57)") (class "Default")
      (node (ref "J4") (pin "57") (pinfunction "57_57") (pintype "passive"))
    )
    (net (code "170") (name "unconnected-(J5-Pad1)") (class "Default")
      (node (ref "J5") (pin "1") (pinfunction "1_1") (pintype "passive"))
    )
    (net (code "171") (name "unconnected-(J5-Pad2)") (class "Default")
      (node (ref "J5") (pin "2") (pinfunction "2_2") (pintype "passive"))
    )
    (net (code "172") (name "unconnected-(J5-Pad3)") (class "Default")
      (node (ref "J5") (pin "3") (pinfunction "3_3") (pintype "passive"))
    )
    (net (code "173") (name "unconnected-(J5-Pad4)") (class "Default")
      (node (ref "J5") (pin "4") (pinfunction "4_4") (pintype "passive"))
    )
    (net (code "174") (name "unconnected-(J5-Pad11)") (class "Default")
      (node (ref "J5") (pin "11") (pinfunction "11_11") (pintype "passive"))
    )
    (net (code "175") (name "unconnected-(J5-Pad12)") (class "Default")
      (node (ref "J5") (pin "12") (pinfunction "12_12") (pintype "passive"))
    )
    (net (code "176") (name "unconnected-(J5-Pad13)") (class "Default")
      (node (ref "J5") (pin "13") (pinfunction "13_13") (pintype "passive"))
    )
    (net (code "177") (name "unconnected-(J5-Pad14)") (class "Default")
      (node (ref "J5") (pin "14") (pinfunction "14_14") (pintype "passive"))
    )
    (net (code "178") (name "unconnected-(J5-Pad15)") (class "Default")
      (node (ref "J5") (pin "15") (pinfunction "15_15") (pintype "passive"))
    )
    (net (code "179") (name "unconnected-(J5-Pad22)") (class "Default")
      (node (ref "J5") (pin "22") (pinfunction "22_22") (pintype "passive"))
    )
    (net (code "180") (name "unconnected-(J5-Pad23)") (class "Default")
      (node (ref "J5") (pin "23") (pinfunction "23_23") (pintype "passive"))
    )
    (net (code "181") (name "unconnected-(J5-Pad24)") (class "Default")
      (node (ref "J5") (pin "24") (pinfunction "24_24") (pintype "passive"))
    )
    (net (code "182") (name "unconnected-(J5-Pad25)") (class "Default")
      (node (ref "J5") (pin "25") (pinfunction "25_25") (pintype "passive"))
    )
    (net (code "183") (name "unconnected-(J5-Pad33)") (class "Default")
      (node (ref "J5") (pin "33") (pinfunction "33_33") (pintype "passive"))
    )
    (net (code "184") (name "unconnected-(J5-Pad34)") (class "Default")
      (node (ref "J5") (pin "34") (pinfunction "34_34") (pintype "passive"))
    )
    (net (code "185") (name "unconnected-(J5-Pad35)") (class "Default")
      (node (ref "J5") (pin "35") (pinfunction "35_35") (pintype "passive"))
    )
    (net (code "186") (name "unconnected-(J5-Pad36)") (class "Default")
      (node (ref "J5") (pin "36") (pinfunction "36_36") (pintype "passive"))
    )
    (net (code "187") (name "unconnected-(J5-Pad43)") (class "Default")
      (node (ref "J5") (pin "43") (pinfunction "43_43") (pintype "passive"))
    )
    (net (code "188") (name "unconnected-(J5-Pad44)") (class "Default")
      (node (ref "J5") (pin "44") (pinfunction "44_44") (pintype "passive"))
    )
    (net (code "189") (name "unconnected-(J5-Pad45)") (class "Default")
      (node (ref "J5") (pin "45") (pinfunction "45_45") (pintype "passive"))
    )
    (net (code "190") (name "unconnected-(J5-Pad46)") (class "Default")
      (node (ref "J5") (pin "46") (pinfunction "46_46") (pintype "passive"))
    )
    (net (code "191") (name "unconnected-(J5-Pad47)") (class "Default")
      (node (ref "J5") (pin "47") (pinfunction "47_47") (pintype "passive"))
    )
    (net (code "192") (name "unconnected-(J5-Pad54)") (class "Default")
      (node (ref "J5") (pin "54") (pinfunction "54_54") (pintype "passive"))
    )
    (net (code "193") (name "unconnected-(J5-Pad55)") (class "Default")
      (node (ref "J5") (pin "55") (pinfunction "55_55") (pintype "passive"))
    )
    (net (code "194") (name "unconnected-(J5-Pad56)") (class "Default")
      (node (ref "J5") (pin "56") (pinfunction "56_56") (pintype "passive"))
    )
    (net (code "195") (name "unconnected-(J5-Pad57)") (class "Default")
      (node (ref "J5") (pin "57") (pinfunction "57_57") (pintype "passive"))
    )
    (net (code "196") (name "unconnected-(J6-Pad1)") (class "Default")
      (node (ref "J6") (pin "1") (pinfunction "1_1") (pintype "passive"))
    )
    (net (code "197") (name "unconnected-(J6-Pad2)") (class "Default")
      (node (ref "J6") (pin "2") (pinfunction "2_2") (pintype "passive"))
    )
    (net (code "198") (name "unconnected-(J6-Pad3)") (class "Default")
      (node (ref "J6") (pin "3") (pinfunction "3_3") (pintype "passive"))
    )
    (net (code "199") (name "unconnected-(J6-Pad4)") (class "Default")
      (node (ref "J6") (pin "4") (pinfunction "4_4") (pintype "passive"))
    )
    (net (code "200") (name "unconnected-(J6-Pad11)") (class "Default")
      (node (ref "J6") (pin "11") (pinfunction "11_11") (pintype "passive"))
    )
    (net (code "201") (name "unconnected-(J6-Pad12)") (class "Default")
      (node (ref "J6") (pin "12") (pinfunction "12_12") (pintype "passive"))
    )
    (net (code "202") (name "unconnected-(J6-Pad13)") (class "Default")
      (node (ref "J6") (pin "13") (pinfunction "13_13") (pintype "passive"))
    )
    (net (code "203") (name "unconnected-(J6-Pad14)") (class "Default")
      (node (ref "J6") (pin "14") (pinfunction "14_14") (pintype "passive"))
    )
    (net (code "204") (name "unconnected-(J6-Pad15)") (class "Default")
      (node (ref "J6") (pin "15") (pinfunction "15_15") (pintype "passive"))
    )
    (net (code "205") (name "unconnected-(J6-Pad22)") (class "Default")
      (node (ref "J6") (pin "22") (pinfunction "22_22") (pintype "passive"))
    )
    (net (code "206") (name "unconnected-(J6-Pad23)") (class "Default")
      (node (ref "J6") (pin "23") (pinfunction "23_23") (pintype "passive"))
    )
    (net (code "207") (name "unconnected-(J6-Pad24)") (class "Default")
      (node (ref "J6") (pin "24") (pinfunction "24_24") (pintype "passive"))
    )
    (net (code "208") (name "unconnected-(J6-Pad25)") (class "Default")
      (node (ref "J6") (pin "25") (pinfunction "25_25") (pintype "passive"))
    )
    (net (code "209") (name "unconnected-(J6-Pad33)") (class "Default")
      (node (ref "J6") (pin "33") (pinfunction "33_33") (pintype "passive"))
    )
    (net (code "210") (name "unconnected-(J6-Pad34)") (class "Default")
      (node (ref "J6") (pin "34") (pinfunction "34_34") (pintype "passive"))
    )
    (net (code "211") (name "unconnected-(J6-Pad35)") (class "Default")
      (node (ref "J6") (pin "35") (pinfunction "35_35") (pintype "passive"))
    )
    (net (code "212") (name "unconnected-(J6-Pad36)") (class "Default")
      (node (ref "J6") (pin "36") (pinfunction "36_36") (pintype "passive"))
    )
    (net (code "213") (name "unconnected-(J6-Pad43)") (class "Default")
      (node (ref "J6") (pin "43") (pinfunction "43_43") (pintype "passive"))
    )
    (net (code "214") (name "unconnected-(J6-Pad44)") (class "Default")
      (node (ref "J6") (pin "44") (pinfunction "44_44") (pintype "passive"))
    )
    (net (code "215") (name "unconnected-(J6-Pad45)") (class "Default")
      (node (ref "J6") (pin "45") (pinfunction "45_45") (pintype "passive"))
    )
    (net (code "216") (name "unconnected-(J6-Pad46)") (class "Default")
      (node (ref "J6") (pin "46") (pinfunction "46_46") (pintype "passive"))
    )
    (net (code "217") (name "unconnected-(J6-Pad47)") (class "Default")
      (node (ref "J6") (pin "47") (pinfunction "47_47") (pintype "passive"))
    )
    (net (code "218") (name "unconnected-(J6-Pad54)") (class "Default")
      (node (ref "J6") (pin "54") (pinfunction "54_54") (pintype "passive"))
    )
    (net (code "219") (name "unconnected-(J6-Pad55)") (class "Default")
      (node (ref "J6") (pin "55") (pinfunction "55_55") (pintype "passive"))
    )
    (net (code "220") (name "unconnected-(J6-Pad56)") (class "Default")
      (node (ref "J6") (pin "56") (pinfunction "56_56") (pintype "passive"))
    )
    (net (code "221") (name "unconnected-(J6-Pad57)") (class "Default")
      (node (ref "J6") (pin "57") (pinfunction "57_57") (pintype "passive"))
    )
    (net (code "222") (name "unconnected-(J7-Pad1)") (class "Default")
      (node (ref "J7") (pin "1") (pinfunction "1_1") (pintype "passive"))
    )
    (net (code "223") (name "unconnected-(J7-Pad2)") (class "Default")
      (node (ref "J7") (pin "2") (pinfunction "2_2") (pintype "passive"))
    )
    (net (code "224") (name "unconnected-(J7-Pad3)") (class "Default")
      (node (ref "J7") (pin "3") (pinfunction "3_3") (pintype "passive"))
    )
    (net (code "225") (name "unconnected-(J7-Pad4)") (class "Default")
      (node (ref "J7") (pin "4") (pinfunction "4_4") (pintype "passive"))
    )
    (net (code "226") (name "unconnected-(J7-Pad11)") (class "Default")
      (node (ref "J7") (pin "11") (pinfunction "11_11") (pintype "passive"))
    )
    (net (code "227") (name "unconnected-(J7-Pad12)") (class "Default")
      (node (ref "J7") (pin "12") (pinfunction "12_12") (pintype "passive"))
    )
    (net (code "228") (name "unconnected-(J7-Pad13)") (class "Default")
      (node (ref "J7") (pin "13") (pinfunction "13_13") (pintype "passive"))
    )
    (net (code "229") (name "unconnected-(J7-Pad14)") (class "Default")
      (node (ref "J7") (pin "14") (pinfunction "14_14") (pintype "passive"))
    )
    (net (code "230") (name "unconnected-(J7-Pad15)") (class "Default")
      (node (ref "J7") (pin "15") (pinfunction "15_15") (pintype "passive"))
    )
    (net (code "231") (name "unconnected-(J7-Pad22)") (class "Default")
      (node (ref "J7") (pin "22") (pinfunction "22_22") (pintype "passive"))
    )
    (net (code "232") (name "unconnected-(J7-Pad23)") (class "Default")
      (node (ref "J7") (pin "23") (pinfunction "23_23") (pintype "passive"))
    )
    (net (code "233") (name "unconnected-(J7-Pad24)") (class "Default")
      (node (ref "J7") (pin "24") (pinfunction "24_24") (pintype "passive"))
    )
    (net (code "234") (name "unconnected-(J7-Pad25)") (class "Default")
      (node (ref "J7") (pin "25") (pinfunction "25_25") (pintype "passive"))
    )
    (net (code "235") (name "unconnected-(J7-Pad33)") (class "Default")
      (node (ref "J7") (pin "33") (pinfunction "33_33") (pintype "passive"))
    )
    (net (code "236") (name "unconnected-(J7-Pad34)") (class "Default")
      (node (ref "J7") (pin "34") (pinfunction "34_34") (pintype "passive"))
    )
    (net (code "237") (name "unconnected-(J7-Pad35)") (class "Default")
      (node (ref "J7") (pin "35") (pinfunction "35_35") (pintype "passive"))
    )
    (net (code "238") (name "unconnected-(J7-Pad36)") (class "Default")
      (node (ref "J7") (pin "36") (pinfunction "36_36") (pintype "passive"))
    )
    (net (code "239") (name "unconnected-(J7-Pad43)") (class "Default")
      (node (ref "J7") (pin "43") (pinfunction "43_43") (pintype "passive"))
    )
    (net (code "240") (name "unconnected-(J7-Pad44)") (class "Default")
      (node (ref "J7") (pin "44") (pinfunction "44_44") (pintype "passive"))
    )
    (net (code "241") (name "unconnected-(J7-Pad45)") (class "Default")
      (node (ref "J7") (pin "45") (pinfunction "45_45") (pintype "passive"))
    )
    (net (code "242") (name "unconnected-(J7-Pad46)") (class "Default")
      (node (ref "J7") (pin "46") (pinfunction "46_46") (pintype "passive"))
    )
    (net (code "243") (name "unconnected-(J7-Pad47)") (class "Default")
      (node (ref "J7") (pin "47") (pinfunction "47_47") (pintype "passive"))
    )
    (net (code "244") (name "unconnected-(J7-Pad54)") (class "Default")
      (node (ref "J7") (pin "54") (pinfunction "54_54") (pintype "passive"))
    )
    (net (code "245") (name "unconnected-(J7-Pad55)") (class "Default")
      (node (ref "J7") (pin "55") (pinfunction "55_55") (pintype "passive"))
    )
    (net (code "246") (name "unconnected-(J7-Pad56)") (class "Default")
      (node (ref "J7") (pin "56") (pinfunction "56_56") (pintype "passive"))
    )
    (net (code "247") (name "unconnected-(J7-Pad57)") (class "Default")
      (node (ref "J7") (pin "57") (pinfunction "57_57") (pintype "passive"))
    )
    (net (code "248") (name "unconnected-(J8-Pad1)") (class "Default")
      (node (ref "J8") (pin "1") (pinfunction "1_1") (pintype "passive"))
    )
    (net (code "249") (name "unconnected-(J8-Pad2)") (class "Default")
      (node (ref "J8") (pin "2") (pinfunction "2_2") (pintype "passive"))
    )
    (net (code "250") (name "unconnected-(J8-Pad3)") (class "Default")
      (node (ref "J8") (pin "3") (pinfunction "3_3") (pintype "passive"))
    )
    (net (code "251") (name "unconnected-(J8-Pad4)") (class "Default")
      (node (ref "J8") (pin "4") (pinfunction "4_4") (pintype "passive"))
    )
    (net (code "252") (name "unconnected-(J8-Pad11)") (class "Default")
      (node (ref "J8") (pin "11") (pinfunction "11_11") (pintype "passive"))
    )
    (net (code "253") (name "unconnected-(J8-Pad12)") (class "Default")
      (node (ref "J8") (pin "12") (pinfunction "12_12") (pintype "passive"))
    )
    (net (code "254") (name "unconnected-(J8-Pad13)") (class "Default")
      (node (ref "J8") (pin "13") (pinfunction "13_13") (pintype "passive"))
    )
    (net (code "255") (name "unconnected-(J8-Pad14)") (class "Default")
      (node (ref "J8") (pin "14") (pinfunction "14_14") (pintype "passive"))
    )
    (net (code "256") (name "unconnected-(J8-Pad15)") (class "Default")
      (node (ref "J8") (pin "15") (pinfunction "15_15") (pintype "passive"))
    )
    (net (code "257") (name "unconnected-(J8-Pad22)") (class "Default")
      (node (ref "J8") (pin "22") (pinfunction "22_22") (pintype "passive"))
    )
    (net (code "258") (name "unconnected-(J8-Pad23)") (class "Default")
      (node (ref "J8") (pin "23") (pinfunction "23_23") (pintype "passive"))
    )
    (net (code "259") (name "unconnected-(J8-Pad24)") (class "Default")
      (node (ref "J8") (pin "24") (pinfunction "24_24") (pintype "passive"))
    )
    (net (code "260") (name "unconnected-(J8-Pad25)") (class "Default")
      (node (ref "J8") (pin "25") (pinfunction "25_25") (pintype "passive"))
    )
    (net (code "261") (name "unconnected-(J8-Pad33)") (class "Default")
      (node (ref "J8") (pin "33") (pinfunction "33_33") (pintype "passive"))
    )
    (net (code "262") (name "unconnected-(J8-Pad34)") (class "Default")
      (node (ref "J8") (pin "34") (pinfunction "34_34") (pintype "passive"))
    )
    (net (code "263") (name "unconnected-(J8-Pad35)") (class "Default")
      (node (ref "J8") (pin "35") (pinfunction "35_35") (pintype "passive"))
    )
    (net (code "264") (name "unconnected-(J8-Pad36)") (class "Default")
      (node (ref "J8") (pin "36") (pinfunction "36_36") (pintype "passive"))
    )
    (net (code "265") (name "unconnected-(J8-Pad43)") (class "Default")
      (node (ref "J8") (pin "43") (pinfunction "43_43") (pintype "passive"))
    )
    (net (code "266") (name "unconnected-(J8-Pad44)") (class "Default")
      (node (ref "J8") (pin "44") (pinfunction "44_44") (pintype "passive"))
    )
    (net (code "267") (name "unconnected-(J8-Pad45)") (class "Default")
      (node (ref "J8") (pin "45") (pinfunction "45_45") (pintype "passive"))
    )
    (net (code "268") (name "unconnected-(J8-Pad46)") (class "Default")
      (node (ref "J8") (pin "46") (pinfunction "46_46") (pintype "passive"))
    )
    (net (code "269") (name "unconnected-(J8-Pad47)") (class "Default")
      (node (ref "J8") (pin "47") (pinfunction "47_47") (pintype "passive"))
    )
    (net (code "270") (name "unconnected-(J8-Pad54)") (class "Default")
      (node (ref "J8") (pin "54") (pinfunction "54_54") (pintype "passive"))
    )
    (net (code "271") (name "unconnected-(J8-Pad55)") (class "Default")
      (node (ref "J8") (pin "55") (pinfunction "55_55") (pintype "passive"))
    )
    (net (code "272") (name "unconnected-(J8-Pad56)") (class "Default")
      (node (ref "J8") (pin "56") (pinfunction "56_56") (pintype "passive"))
    )
    (net (code "273") (name "unconnected-(J8-Pad57)") (class "Default")
      (node (ref "J8") (pin "57") (pinfunction "57_57") (pintype "passive"))
    )
  )
)
